# Sheet1.net
KiCad netlist of a schematic drawn in Altium Designer
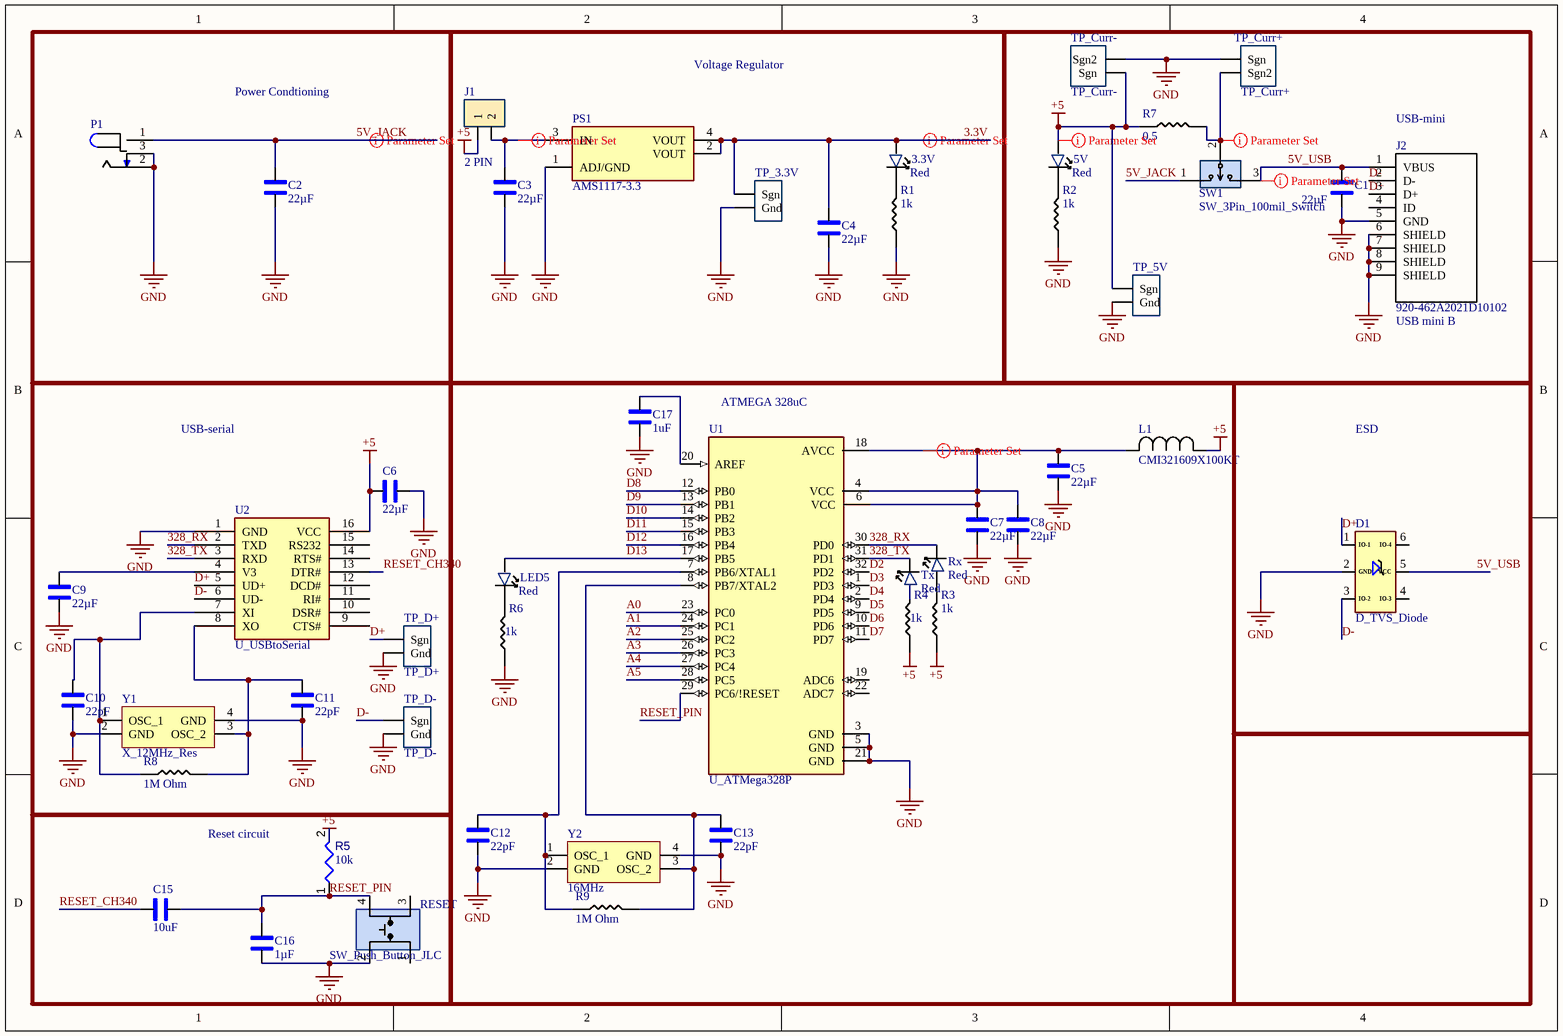
[diagram p0: Sheet1.SchDoc]

(export (version "E")
  (design (tool "Eeschema 10.0.6"))
  (components
    (comp (ref "3.3V")
      (value "Red")
      (footprint "LED_1206")
      (description "Red 621~631nm 1206 Light Emitting Diodes (LED) RoHS")
      (fields (field (name "LCSC PART#") "C93133") (field (name "MFR PART #") "15-21/R6C-FQ1R1B/2T"))
      (libsource (lib "University of Colorado") (part "LED_YELLOW_1206"))
    )
    (comp (ref "5V")
      (value "Red")
      (footprint "LED_1206")
      (description "Red 621~631nm 1206 Light Emitting Diodes (LED) RoHS")
      (fields (field (name "LCSC PART#") "C93133") (field (name "MFR PART #") "15-21/R6C-FQ1R1B/2T"))
      (libsource (lib "University of Colorado") (part "LED_YELLOW_1206"))
    )
    (comp (ref "C1")
      (value "22µF")
      (footprint "1206_Passive_Capacitor")
      (description "22uF ±10% 25V X5R 1206 Multilayer Ceramic Capacitors MLCC - SMD/SMT RoHS")
      (fields (field (name "LCSC PART#") "C12891") (field (name "MFR PART #") "CL31A226KAHNNNE"))
      (libsource (lib "University of Colorado") (part "C_47nF_1206"))
    )
    (comp (ref "C2")
      (value "22µF")
      (footprint "1206_Passive_Capacitor")
      (description "22uF ±10% 25V X5R 1206 Multilayer Ceramic Capacitors MLCC - SMD/SMT RoHS")
      (fields (field (name "LCSC PART#") "C12891") (field (name "MFR PART #") "CL31A226KAHNNNE"))
      (libsource (lib "University of Colorado") (part "C_47nF_1206"))
    )
    (comp (ref "C3")
      (value "22µF")
      (footprint "1206_Passive_Capacitor")
      (description "22uF ±10% 25V X5R 1206 Multilayer Ceramic Capacitors MLCC - SMD/SMT RoHS")
      (fields (field (name "LCSC PART#") "C12891") (field (name "MFR PART #") "CL31A226KAHNNNE"))
      (libsource (lib "University of Colorado") (part "C_47nF_1206"))
    )
    (comp (ref "C4")
      (value "22µF")
      (footprint "1206_Passive_Capacitor")
      (description "22uF ±10% 25V X5R 1206 Multilayer Ceramic Capacitors MLCC - SMD/SMT RoHS")
      (fields (field (name "LCSC PART#") "C12891") (field (name "MFR PART #") "CL31A226KAHNNNE"))
      (libsource (lib "University of Colorado") (part "C_47nF_1206"))
    )
    (comp (ref "C5")
      (value "22µF")
      (footprint "1206_Passive_Capacitor")
      (description "22uF ±10% 25V X5R 1206 Multilayer Ceramic Capacitors MLCC - SMD/SMT RoHS")
      (fields (field (name "LCSC PART#") "C12891") (field (name "MFR PART #") "CL31A226KAHNNNE"))
      (libsource (lib "University of Colorado") (part "C_47nF_1206"))
    )
    (comp (ref "C6")
      (value "22µF")
      (footprint "1206_Passive_Capacitor")
      (description "22uF ±10% 25V X5R 1206 Multilayer Ceramic Capacitors MLCC - SMD/SMT RoHS")
      (fields (field (name "LCSC PART#") "C12891") (field (name "MFR PART #") "CL31A226KAHNNNE"))
      (libsource (lib "University of Colorado") (part "C_47nF_1206"))
    )
    (comp (ref "C7")
      (value "22µF")
      (footprint "1206_Passive_Capacitor")
      (description "22uF ±10% 25V X5R 1206 Multilayer Ceramic Capacitors MLCC - SMD/SMT RoHS")
      (fields (field (name "LCSC PART#") "C12891") (field (name "MFR PART #") "CL31A226KAHNNNE"))
      (libsource (lib "University of Colorado") (part "C_47nF_1206"))
    )
    (comp (ref "C8")
      (value "22µF")
      (footprint "1206_Passive_Capacitor")
      (description "22uF ±10% 25V X5R 1206 Multilayer Ceramic Capacitors MLCC - SMD/SMT RoHS")
      (fields (field (name "LCSC PART#") "C12891") (field (name "MFR PART #") "CL31A226KAHNNNE"))
      (libsource (lib "University of Colorado") (part "C_47nF_1206"))
    )
    (comp (ref "C9")
      (value "22µF")
      (footprint "1206_Passive_Capacitor")
      (description "22uF ±10% 25V X5R 1206 Multilayer Ceramic Capacitors MLCC - SMD/SMT RoHS")
      (fields (field (name "LCSC PART#") "C12891") (field (name "MFR PART #") "CL31A226KAHNNNE"))
      (libsource (lib "University of Colorado") (part "C_47nF_1206"))
    )
    (comp (ref "C10")
      (value "22pF")
      (footprint "1206_Passive_Capacitor")
      (description "22uF ±10% 25V X5R 1206 Multilayer Ceramic Capacitors MLCC - SMD/SMT RoHS")
      (fields (field (name "LCSC PART#") "C12891") (field (name "MFR PART #") "CL31A226KAHNNNE"))
      (libsource (lib "University of Colorado") (part "C_47nF_1206"))
    )
    (comp (ref "C11")
      (value "22pF")
      (footprint "1206_Passive_Capacitor")
      (description "22uF ±10% 25V X5R 1206 Multilayer Ceramic Capacitors MLCC - SMD/SMT RoHS")
      (fields (field (name "LCSC PART#") "C12891") (field (name "MFR PART #") "CL31A226KAHNNNE"))
      (libsource (lib "University of Colorado") (part "C_47nF_1206"))
    )
    (comp (ref "C12")
      (value "22pF")
      (footprint "1206_Passive_Capacitor")
      (description "22uF ±10% 25V X5R 1206 Multilayer Ceramic Capacitors MLCC - SMD/SMT RoHS")
      (fields (field (name "LCSC PART#") "C12891") (field (name "MFR PART #") "CL31A226KAHNNNE"))
      (libsource (lib "University of Colorado") (part "C_47nF_1206"))
    )
    (comp (ref "C13")
      (value "22pF")
      (footprint "1206_Passive_Capacitor")
      (description "22uF ±10% 25V X5R 1206 Multilayer Ceramic Capacitors MLCC - SMD/SMT RoHS")
      (fields (field (name "LCSC PART#") "C12891") (field (name "MFR PART #") "CL31A226KAHNNNE"))
      (libsource (lib "University of Colorado") (part "C_47nF_1206"))
    )
    (comp (ref "C15")
      (value "10uF")
      (footprint "1206_Passive_Capacitor")
      (description "10uF ±10% 50V X5R 1206 Multilayer Ceramic Capacitors MLCC - SMD/SMT RoHS")
      (fields (field (name "LCSC PART#") "C13585") (field (name "MFR PART #") "CL31A106KBHNNNE"))
      (libsource (lib "ECEN5730Lib_2023_05_DS") (part "C_10uF_1206"))
    )
    (comp (ref "C16")
      (value "1µF")
      (footprint "1206_Passive_Capacitor")
      (description "MULTILAYER CERAMIC CAPACITORS MLCC - SMD/SMT 1UF 50V 1206 ROHS")
      (fields (field (name "MFR PART #") "CL31B105KBHNNNE") (field (name "LCSC PART#") "C1848"))
      (libsource (lib "University of Colorado") (part "C_47nF_1206"))
    )
    (comp (ref "C17")
      (value "1uF")
      (footprint "1206_Passive_Capacitor")
      (description "MULTILAYER CERAMIC CAPACITORS MLCC - SMD/SMT 1UF 50V 1206 ROHS")
      (fields (field (name "MFR PART #") "CL31B105KBHNNNE") (field (name "LCSC PART#") "C1848"))
      (libsource (lib "ECEN5730Lib_2023_05_DS") (part "C_1uF_1206"))
    )
    (comp (ref "D1")
      (value "D_TVS_Diode")
      (footprint "TVS")
      (description "TVS SOT-23-6 ROHS")
      (fields (field (name "LCSC PART#") "C85364") (field (name "MFR PART #") "SRV05-4-P-T7"))
      (libsource (lib "University of Colorado") (part "D_TVS_Diode"))
    )
    (comp (ref "J1")
      (value "2 PIN")
      (footprint "2_PIN_100MIL")
      (description "2.54mm Straight 2 1 Header,Breakaway Through Hole,P=2.54mm Pin Header & Female Header ROHS")
      (fields (field (name "LCSC PART#") "C124375") (field (name "MFR PART #") "B-2100S02P-A110"))
      (libsource (lib "University of Colorado") (part "JM_2_PIN_MALE"))
    )
    (comp (ref "J2")
      (value "USB mini B")
      (footprint "USB_MINI_B")
      (description "Through Hole USB Connectors RoHS")
      (fields
        (field (name "LCSC PART#") "C46398")
        (field (name "MFR PART #") "920-462A2021D10102")
        (field (name "Comment") "J_USB_B_Mini")
      )
      (libsource (lib "University of Colorado") (part "J_USB_B_Mini"))
    )
    (comp (ref "L1")
      (value "FB_10uH_1206")
      (footprint "AIML-1206_ABR-M")
      (description "25mA 10uH ±10% 800mO 1206  Inductors (SMD) ROHS")
      (fields (field (name "LCSC PART#") "C1051") (field (name "MFR PART #") "CMI321609X100KT"))
      (libsource (lib "University of Colorado") (part "FB_10uH_1206"))
    )
    (comp (ref "LED5")
      (value "Red")
      (footprint "LED_1206")
      (description "Red 621~631nm 1206 Light Emitting Diodes (LED) RoHS")
      (fields (field (name "LCSC PART#") "C93133") (field (name "MFR PART #") "15-21/R6C-FQ1R1B/2T"))
      (libsource (lib "University of Colorado") (part "LED_YELLOW_1206"))
    )
    (comp (ref "P1")
      (value "P_Power Jack")
      (footprint "Power_Jack")
      (description "Power Barrel Connector Jack 2.10mm ID (0.083\"), 5.50mm OD (0.217\") Through Hole, Right Angle")
      (fields (field (name "LCSC PART#") "C136744") (field (name "MFR PART #") "PJ-102A"))
      (libsource (lib "University of Colorado") (part "P_Power Jack"))
    )
    (comp (ref "PS1")
      (value "PS_AMS_LDO_3v3")
      (footprint "LDO")
      (description "LOW DROPOUT REGULATORS(LDO) POSITIVE FIXED 1.3V @ 800MA 15V 3.3V 1A SOT-223 ROHS")
      (fields (field (name "MFR PART #") "AMS1117-3.3") (field (name "LCSC PART#") "C6186"))
      (libsource (lib "University of Colorado") (part "PS_AMS_LDO_3v3"))
    )
    (comp (ref "R1")
      (value "1k")
      (footprint "1206_Passive_Resitor")
      (description "CHIP RESISTOR - SURFACE MOUNT 1KOHMS ±1% 1/4W 1206 ROHS")
      (fields (field (name "LCSC PART#") "C4410") (field (name "MFR PART #") "RNCP1206FTD1K00CT"))
      (libsource (lib "University of Colorado") (part "R_500mOhm_1206"))
    )
    (comp (ref "R2")
      (value "1k")
      (footprint "1206_Passive_Resitor")
      (description "CHIP RESISTOR - SURFACE MOUNT 1KOHMS ±1% 1/4W 1206 ROHS")
      (fields (field (name "LCSC PART#") "C4410") (field (name "MFR PART #") "RNCP1206FTD1K00CT"))
      (libsource (lib "University of Colorado") (part "R_500mOhm_1206"))
    )
    (comp (ref "R3")
      (value "1k")
      (footprint "1206_Passive_Resitor")
      (description "CHIP RESISTOR - SURFACE MOUNT 1KOHMS ±1% 1/4W 1206 ROHS")
      (fields (field (name "LCSC PART#") "C4410") (field (name "MFR PART #") "RNCP1206FTD1K00CT"))
      (libsource (lib "University of Colorado") (part "R_500mOhm_1206"))
    )
    (comp (ref "R4")
      (value "1k")
      (footprint "1206_Passive_Resitor")
      (description "CHIP RESISTOR - SURFACE MOUNT 1KOHMS ±1% 1/4W 1206 ROHS")
      (fields (field (name "LCSC PART#") "C4410") (field (name "MFR PART #") "RNCP1206FTD1K00CT"))
      (libsource (lib "University of Colorado") (part "R_500mOhm_1206"))
    )
    (comp (ref "R5")
      (value "10k")
      (footprint "RESC3216X60X45ML15T20")
      (description "Chip Resistor, 10 KOhm, +/- 1%, 0.25 W, -55 to 155 degC, 1206 (3216 Metric)")
      (fields (field (name "TOLERANCE") "1%") (field (name "POWER") "250mW"))
      (libsource (lib "University of Colorado") (part "RES-2"))
    )
    (comp (ref "R6")
      (value "1k")
      (footprint "1206_Passive_Resitor")
      (description "CHIP RESISTOR - SURFACE MOUNT 1KOHMS ±1% 1/4W 1206 ROHS")
      (fields (field (name "LCSC PART#") "C4410") (field (name "MFR PART #") "RNCP1206FTD1K00CT"))
      (libsource (lib "University of Colorado") (part "R_500mOhm_1206"))
    )
    (comp (ref "R7")
      (value "0.5")
      (footprint "1206_Passive_Resitor")
      (description "Resistors/Shunt 250mW 500mO ±800ppm/? ±5% 1206  Current Sense  Resistors ROHS")
      (fields (field (name "MFR PART #") "1206W4J050KT5E") (field (name "LCSC PART#") "C247433"))
      (libsource (lib "University of Colorado") (part "R_500mOhm_1206"))
    )
    (comp (ref "R8")
      (value "1M Ohm")
      (footprint "1206_Passive_Resitor")
      (description "CHIP RESISTOR - SURFACE MOUNT 1MOHMS ±1% 1/4W 1206 ROHS")
      (fields (field (name "MFR PART #") "RMCF1206JT1M00") (field (name "LCSC PART#") "C17927"))
      (libsource (lib "ECEN5730Lib_2023_05_DS") (part "R_1M_1206"))
    )
    (comp (ref "R9")
      (value "1M Ohm")
      (footprint "1206_Passive_Resitor")
      (description "CHIP RESISTOR - SURFACE MOUNT 1MOHMS ±1% 1/4W 1206 ROHS")
      (fields (field (name "MFR PART #") "RMCF1206JT1M00") (field (name "LCSC PART#") "C17927"))
      (libsource (lib "ECEN5730Lib_2023_05_DS") (part "R_1M_1206"))
    )
    (comp (ref "RESET")
      (value "SW_Push_Button_JLC")
      (footprint "Switch_JLC")
      (description "Tactile Switch SPST-NO Top Actuated Surface Mount")
      (fields (field (name "MFR PART #") "KH-4.5X4.5X4.3H-STM") (field (name "LCSC PART#") "C2837550"))
      (libsource (lib "University of Colorado") (part "SW_Push_Button_JLC"))
    )
    (comp (ref "Rx")
      (value "Red")
      (footprint "LED_1206")
      (description "Red 621~631nm 1206 Light Emitting Diodes (LED) RoHS")
      (fields (field (name "LCSC PART#") "C93133") (field (name "MFR PART #") "15-21/R6C-FQ1R1B/2T"))
      (libsource (lib "University of Colorado") (part "LED_YELLOW_1206"))
    )
    (comp (ref "SW1")
      (value "SW_3Pin_100mil_Switch")
      (footprint "3_PIN_100mil")
      (description "Connector Header Through Hole 3 position 0.100\" (2.54mm)")
      (fields (field (name "LCSC PART#") "C49257") (field (name "MFR PART #") "PREC003SAAN-RC"))
      (libsource (lib "University of Colorado") (part "SW_3Pin_100mil_Switch"))
    )
    (comp (ref "TP_3.3V")
      (value "TP_10x_Probe")
      (footprint "TP10x_Probe")
      (description "Test Point 300 mil centers")
      (libsource (lib "University of Colorado") (part "TP_10x_Probe"))
    )
    (comp (ref "TP_5V")
      (value "TP_10x_Probe")
      (footprint "TP10x_Probe")
      (description "Test Point 300 mil centers")
      (libsource (lib "University of Colorado") (part "TP_10x_Probe"))
    )
    (comp (ref "TP_Curr+")
      (value "TP_Curr+")
      (footprint "TP_Diff_Probe")
      (description "Test Point 300 mil centers")
      (libsource (lib "") (part "TP_Diff_Probe_1"))
    )
    (comp (ref "TP_Curr-")
      (value "TP_Curr-")
      (footprint "TP_Diff_Probe")
      (description "Test Point 300 mil centers")
      (libsource (lib "University of Colorado") (part "TP_Diff_Probe"))
    )
    (comp (ref "TP_D+")
      (value "TP_D+")
      (footprint "TP10x_Probe")
      (description "Test Point 300 mil centers")
      (libsource (lib "University of Colorado") (part "TP_10x_Probe"))
    )
    (comp (ref "TP_D-")
      (value "TP_D-")
      (footprint "TP10x_Probe")
      (description "Test Point 300 mil centers")
      (libsource (lib "University of Colorado") (part "TP_10x_Probe"))
    )
    (comp (ref "Tx")
      (value "Red")
      (footprint "LED_1206")
      (description "Red 621~631nm 1206 Light Emitting Diodes (LED) RoHS")
      (fields (field (name "LCSC PART#") "C93133") (field (name "MFR PART #") "15-21/R6C-FQ1R1B/2T"))
      (libsource (lib "University of Colorado") (part "LED_YELLOW_1206"))
    )
    (comp (ref "U1")
      (value "U_ATMega328P")
      (footprint "ATMega328P")
      (description "AVR AVR® ATmega Microcontroller IC 8-Bit 20MHz 32KB (16K x 16) FLASH 32-TQFP (7x7)")
      (fields (field (name "MFR PART #") "ATMEGA328P-AU") (field (name "LCSC PART#") "C14877"))
      (libsource (lib "University of Colorado") (part "U_ATMega328P"))
    )
    (comp (ref "U2")
      (value "U_USBtoSerial")
      (footprint "USB to serial")
      (description "Transceiver USB 2.0 2Mbps SOP-16_150mil USB ICs RoHS")
      (fields (field (name "LCSC PART#") "C14267") (field (name "MFR PART #") "CH340G"))
      (libsource (lib "University of Colorado") (part "U_USBtoSerial"))
    )
    (comp (ref "Y1")
      (value "X_12MHz_Res")
      (footprint "Crystal resonator")
      (description "SMD Crystal Resonators 12MHz ±10ppm SMD-3225_4P RoHS")
      (fields (field (name "MFR PART #") "X322512MSB4SI") (field (name "LCSC PART#") "C9002"))
      (libsource (lib "University of Colorado") (part "X_12MHz_Res"))
    )
    (comp (ref "Y2")
      (value "16MHz")
      (footprint "Crystal resonator")
      (description "±10ppm 16000000Hz -40℃~85℃ 贴片无源晶振 60Ω 9pF SMD3225-4P Crystals ROHS")
      (fields (field (name "LCSC PART#") "C13738") (field (name "MFR PART #") "X322516MLB4SI"))
      (libsource (lib "ECEN5730Lib_2023_05_DS") (part "X_16Mhz_Res"))
    )
  )
  (nets
    (net (code "1") (name "+5") (class "Default")
      (node (ref "5V") (pin "1") (pinfunction "1_1") (pintype "passive"))
      (node (ref "C6") (pin "1") (pinfunction "1_1") (pintype "passive"))
      (node (ref "J1") (pin "1") (pinfunction "1_1") (pintype "passive"))
      (node (ref "L1") (pin "1") (pinfunction "1_1") (pintype "passive"))
      (node (ref "R3") (pin "1") (pinfunction "1_1") (pintype "passive"))
      (node (ref "R4") (pin "1") (pinfunction "1_1") (pintype "passive"))
      (node (ref "R5") (pin "2") (pinfunction "2_2") (pintype "passive"))
      (node (ref "R7") (pin "1") (pinfunction "1_1") (pintype "passive"))
      (node (ref "TP_5V") (pin "1") (pinfunction "Sgn_1") (pintype "passive"))
      (node (ref "TP_Curr-") (pin "1") (pinfunction "Sgn_1") (pintype "passive"))
      (node (ref "U2") (pin "16") (pinfunction "VCC_16") (pintype "passive"))
    )
    (net (code "2") (name "/3.3V") (class "Default")
      (node (ref "3.3V") (pin "1") (pinfunction "1_1") (pintype "passive"))
      (node (ref "C4") (pin "1") (pinfunction "1_1") (pintype "passive"))
      (node (ref "PS1") (pin "2") (pinfunction "VOUT_2") (pintype "power_in"))
      (node (ref "PS1") (pin "4") (pinfunction "VOUT_4") (pintype "power_in"))
      (node (ref "TP_3.3V") (pin "1") (pinfunction "Sgn_1") (pintype "passive"))
    )
    (net (code "3") (name "/5V_JACK") (class "Default")
      (node (ref "C2") (pin "2") (pinfunction "2_2") (pintype "passive"))
      (node (ref "P1") (pin "1") (pinfunction "1_1") (pintype "power_in"))
      (node (ref "SW1") (pin "1") (pinfunction "1_1") (pintype "passive"))
    )
    (net (code "4") (name "/5V_USB") (class "Default")
      (node (ref "C1") (pin "2") (pinfunction "2_2") (pintype "passive"))
      (node (ref "D1") (pin "5") (pinfunction "VCC_5") (pintype "passive"))
      (node (ref "J2") (pin "1") (pinfunction "VBUS_1") (pintype "passive"))
      (node (ref "SW1") (pin "3") (pinfunction "3_3") (pintype "passive"))
    )
    (net (code "5") (name "/328_RX") (class "Default")
      (node (ref "Rx") (pin "2") (pinfunction "2_2") (pintype "passive"))
      (node (ref "U1") (pin "30") (pinfunction "PD0_30") (pintype "bidirectional"))
      (node (ref "U2") (pin "2") (pinfunction "TXD_2") (pintype "passive"))
    )
    (net (code "6") (name "/328_TX") (class "Default")
      (node (ref "Tx") (pin "2") (pinfunction "2_2") (pintype "passive"))
      (node (ref "U1") (pin "31") (pinfunction "PD1_31") (pintype "bidirectional"))
      (node (ref "U2") (pin "3") (pinfunction "RXD_3") (pintype "passive"))
    )
    (net (code "7") (name "/A0") (class "Default")
      (node (ref "U1") (pin "23") (pinfunction "PC0_23") (pintype "bidirectional"))
    )
    (net (code "8") (name "/A1") (class "Default")
      (node (ref "U1") (pin "24") (pinfunction "PC1_24") (pintype "bidirectional"))
    )
    (net (code "9") (name "/A2") (class "Default")
      (node (ref "U1") (pin "25") (pinfunction "PC2_25") (pintype "bidirectional"))
    )
    (net (code "10") (name "/A3") (class "Default")
      (node (ref "U1") (pin "26") (pinfunction "PC3_26") (pintype "bidirectional"))
    )
    (net (code "11") (name "/A4") (class "Default")
      (node (ref "U1") (pin "27") (pinfunction "PC4_27") (pintype "bidirectional"))
    )
    (net (code "12") (name "/A5") (class "Default")
      (node (ref "U1") (pin "28") (pinfunction "PC5_28") (pintype "bidirectional"))
    )
    (net (code "13") (name "/D+") (class "Default")
      (node (ref "D1") (pin "1") (pinfunction "IO-1_1") (pintype "passive"))
      (node (ref "J2") (pin "3") (pinfunction "D+_3") (pintype "passive"))
      (node (ref "TP_D+") (pin "1") (pinfunction "Sgn_1") (pintype "passive"))
      (node (ref "U2") (pin "5") (pinfunction "UD+_5") (pintype "passive"))
    )
    (net (code "14") (name "/D-") (class "Default")
      (node (ref "D1") (pin "3") (pinfunction "IO-2_3") (pintype "passive"))
      (node (ref "J2") (pin "2") (pinfunction "D-_2") (pintype "passive"))
      (node (ref "TP_D-") (pin "1") (pinfunction "Sgn_1") (pintype "passive"))
      (node (ref "U2") (pin "6") (pinfunction "UD-_6") (pintype "passive"))
    )
    (net (code "15") (name "/D2") (class "Default")
      (node (ref "U1") (pin "32") (pinfunction "PD2_32") (pintype "bidirectional"))
    )
    (net (code "16") (name "/D3") (class "Default")
      (node (ref "U1") (pin "1") (pinfunction "PD3_1") (pintype "bidirectional"))
    )
    (net (code "17") (name "/D4") (class "Default")
      (node (ref "U1") (pin "2") (pinfunction "PD4_2") (pintype "bidirectional"))
    )
    (net (code "18") (name "/D5") (class "Default")
      (node (ref "U1") (pin "9") (pinfunction "PD5_9") (pintype "bidirectional"))
    )
    (net (code "19") (name "/D6") (class "Default")
      (node (ref "U1") (pin "10") (pinfunction "PD6_10") (pintype "bidirectional"))
    )
    (net (code "20") (name "/D7") (class "Default")
      (node (ref "U1") (pin "11") (pinfunction "PD7_11") (pintype "bidirectional"))
    )
    (net (code "21") (name "/D8") (class "Default")
      (node (ref "U1") (pin "12") (pinfunction "PB0_12") (pintype "bidirectional"))
    )
    (net (code "22") (name "/D9") (class "Default")
      (node (ref "U1") (pin "13") (pinfunction "PB1_13") (pintype "bidirectional"))
    )
    (net (code "23") (name "/D10") (class "Default")
      (node (ref "U1") (pin "14") (pinfunction "PB2_14") (pintype "bidirectional"))
    )
    (net (code "24") (name "/D11") (class "Default")
      (node (ref "U1") (pin "15") (pinfunction "PB3_15") (pintype "bidirectional"))
    )
    (net (code "25") (name "/D12") (class "Default")
      (node (ref "U1") (pin "16") (pinfunction "PB4_16") (pintype "bidirectional"))
    )
    (net (code "26") (name "/D13") (class "Default")
      (node (ref "LED5") (pin "1") (pinfunction "1_1") (pintype "passive"))
      (node (ref "U1") (pin "17") (pinfunction "PB5_17") (pintype "bidirectional"))
    )
    (net (code "27") (name "/RESET_CH340") (class "Default")
      (node (ref "C15") (pin "1") (pinfunction "1_1") (pintype "passive"))
      (node (ref "U2") (pin "13") (pinfunction "DTR#_13") (pintype "passive"))
    )
    (net (code "28") (name "/RESET_PIN") (class "Default")
      (node (ref "C15") (pin "2") (pinfunction "2_2") (pintype "passive"))
      (node (ref "C16") (pin "2") (pinfunction "2_2") (pintype "passive"))
      (node (ref "R5") (pin "1") (pinfunction "1_1") (pintype "passive"))
      (node (ref "RESET") (pin "4") (pinfunction "4_4") (pintype "passive"))
      (node (ref "U1") (pin "29") (pinfunction "PC6/!RESET_29") (pintype "bidirectional"))
    )
    (net (code "29") (name "GND") (class "Default")
      (node (ref "C1") (pin "1") (pinfunction "1_1") (pintype "passive"))
      (node (ref "C10") (pin "1") (pinfunction "1_1") (pintype "passive"))
      (node (ref "C11") (pin "1") (pinfunction "1_1") (pintype "passive"))
      (node (ref "C12") (pin "1") (pinfunction "1_1") (pintype "passive"))
      (node (ref "C13") (pin "1") (pinfunction "1_1") (pintype "passive"))
      (node (ref "C16") (pin "1") (pinfunction "1_1") (pintype "passive"))
      (node (ref "C17") (pin "2") (pinfunction "2_2") (pintype "passive"))
      (node (ref "C2") (pin "1") (pinfunction "1_1") (pintype "passive"))
      (node (ref "C3") (pin "2") (pinfunction "2_2") (pintype "passive"))
      (node (ref "C4") (pin "2") (pinfunction "2_2") (pintype "passive"))
      (node (ref "C5") (pin "1") (pinfunction "1_1") (pintype "passive"))
      (node (ref "C6") (pin "2") (pinfunction "2_2") (pintype "passive"))
      (node (ref "C7") (pin "1") (pinfunction "1_1") (pintype "passive"))
      (node (ref "C8") (pin "1") (pinfunction "1_1") (pintype "passive"))
      (node (ref "C9") (pin "2") (pinfunction "2_2") (pintype "passive"))
      (node (ref "D1") (pin "2") (pinfunction "GND_2") (pintype "passive"))
      (node (ref "J2") (pin "5") (pinfunction "GND_5") (pintype "passive"))
      (node (ref "J2") (pin "6") (pinfunction "SHIELD_6") (pintype "passive"))
      (node (ref "J2") (pin "7") (pinfunction "SHIELD_7") (pintype "passive"))
      (node (ref "J2") (pin "8") (pinfunction "SHIELD_8") (pintype "passive"))
      (node (ref "J2") (pin "9") (pinfunction "SHIELD_9") (pintype "passive"))
      (node (ref "P1") (pin "2") (pinfunction "2_2") (pintype "power_in"))
      (node (ref "P1") (pin "3") (pinfunction "3_3") (pintype "power_in"))
      (node (ref "PS1") (pin "1") (pinfunction "ADJ/GND_1") (pintype "passive"))
      (node (ref "R1") (pin "1") (pinfunction "1_1") (pintype "passive"))
      (node (ref "R2") (pin "1") (pinfunction "1_1") (pintype "passive"))
      (node (ref "R6") (pin "1") (pinfunction "1_1") (pintype "passive"))
      (node (ref "RESET") (pin "2") (pinfunction "2_2") (pintype "passive"))
      (node (ref "TP_3.3V") (pin "2") (pinfunction "Gnd_2") (pintype "passive"))
      (node (ref "TP_5V") (pin "2") (pinfunction "Gnd_2") (pintype "passive"))
      (node (ref "TP_Curr+") (pin "1") (pinfunction "Sgn_1") (pintype "passive"))
      (node (ref "TP_Curr-") (pin "2") (pinfunction "Sgn2_2") (pintype "passive"))
      (node (ref "TP_D+") (pin "2") (pinfunction "Gnd_2") (pintype "passive"))
      (node (ref "TP_D-") (pin "2") (pinfunction "Gnd_2") (pintype "passive"))
      (node (ref "U1") (pin "21") (pinfunction "GND_21") (pintype "power_in"))
      (node (ref "U1") (pin "3") (pinfunction "GND_3") (pintype "power_in"))
      (node (ref "U1") (pin "5") (pinfunction "GND_5") (pintype "power_in"))
      (node (ref "U2") (pin "1") (pinfunction "GND_1") (pintype "passive"))
      (node (ref "Y1") (pin "2") (pinfunction "GND_2") (pintype "passive"))
      (node (ref "Y1") (pin "4") (pinfunction "GND_4") (pintype "passive"))
      (node (ref "Y2") (pin "2") (pinfunction "GND_2") (pintype "passive"))
      (node (ref "Y2") (pin "4") (pinfunction "GND_4") (pintype "passive"))
    )
    (net (code "30") (name "Net-(3.3V-Pad2)") (class "Default")
      (node (ref "3.3V") (pin "2") (pinfunction "2_2") (pintype "passive"))
      (node (ref "R1") (pin "2") (pinfunction "2_2") (pintype "passive"))
    )
    (net (code "31") (name "Net-(5V-Pad2)") (class "Default")
      (node (ref "5V") (pin "2") (pinfunction "2_2") (pintype "passive"))
      (node (ref "R2") (pin "2") (pinfunction "2_2") (pintype "passive"))
    )
    (net (code "32") (name "Net-(LED5-Pad2)") (class "Default")
      (node (ref "LED5") (pin "2") (pinfunction "2_2") (pintype "passive"))
      (node (ref "R6") (pin "2") (pinfunction "2_2") (pintype "passive"))
    )
    (net (code "33") (name "Net-(PS1-IN)") (class "Default")
      (node (ref "C3") (pin "1") (pinfunction "1_1") (pintype "passive"))
      (node (ref "J1") (pin "2") (pinfunction "2_2") (pintype "passive"))
      (node (ref "PS1") (pin "3") (pinfunction "IN_3") (pintype "power_in"))
    )
    (net (code "34") (name "Net-(R3-Pad2)") (class "Default")
      (node (ref "R3") (pin "2") (pinfunction "2_2") (pintype "passive"))
      (node (ref "Rx") (pin "1") (pinfunction "1_1") (pintype "passive"))
    )
    (net (code "35") (name "Net-(R4-Pad2)") (class "Default")
      (node (ref "R4") (pin "2") (pinfunction "2_2") (pintype "passive"))
      (node (ref "Tx") (pin "1") (pinfunction "1_1") (pintype "passive"))
    )
    (net (code "36") (name "Net-(TP_Curr+-Sgn2)") (class "Default")
      (node (ref "R7") (pin "2") (pinfunction "2_2") (pintype "passive"))
      (node (ref "SW1") (pin "2") (pinfunction "2_2") (pintype "passive"))
      (node (ref "TP_Curr+") (pin "2") (pinfunction "Sgn2_2") (pintype "passive"))
    )
    (net (code "37") (name "Net-(U1-AREF)") (class "Default")
      (node (ref "C17") (pin "1") (pinfunction "1_1") (pintype "passive"))
      (node (ref "U1") (pin "20") (pinfunction "AREF_20") (pintype "input"))
    )
    (net (code "38") (name "Net-(U1-AVCC)") (class "Default")
      (node (ref "C5") (pin "2") (pinfunction "2_2") (pintype "passive"))
      (node (ref "C7") (pin "2") (pinfunction "2_2") (pintype "passive"))
      (node (ref "C8") (pin "2") (pinfunction "2_2") (pintype "passive"))
      (node (ref "L1") (pin "2") (pinfunction "2_2") (pintype "passive"))
      (node (ref "U1") (pin "18") (pinfunction "AVCC_18") (pintype "power_in"))
      (node (ref "U1") (pin "4") (pinfunction "VCC_4") (pintype "power_in"))
      (node (ref "U1") (pin "6") (pinfunction "VCC_6") (pintype "power_in"))
    )
    (net (code "39") (name "Net-(U1-PB6{slash}XTAL1)") (class "Default")
      (node (ref "C12") (pin "2") (pinfunction "2_2") (pintype "passive"))
      (node (ref "R9") (pin "1") (pinfunction "1_1") (pintype "passive"))
      (node (ref "U1") (pin "7") (pinfunction "PB6/XTAL1_7") (pintype "bidirectional"))
      (node (ref "Y2") (pin "1") (pinfunction "OSC_1_1") (pintype "passive"))
    )
    (net (code "40") (name "Net-(U1-PB7{slash}XTAL2)") (class "Default")
      (node (ref "C13") (pin "2") (pinfunction "2_2") (pintype "passive"))
      (node (ref "R9") (pin "2") (pinfunction "2_2") (pintype "passive"))
      (node (ref "U1") (pin "8") (pinfunction "PB7/XTAL2_8") (pintype "bidirectional"))
      (node (ref "Y2") (pin "3") (pinfunction "OSC_2_3") (pintype "passive"))
    )
    (net (code "41") (name "Net-(U2-V3)") (class "Default")
      (node (ref "C9") (pin "1") (pinfunction "1_1") (pintype "passive"))
      (node (ref "U2") (pin "4") (pinfunction "V3_4") (pintype "passive"))
    )
    (net (code "42") (name "Net-(U2-XI)") (class "Default")
      (node (ref "C10") (pin "2") (pinfunction "2_2") (pintype "passive"))
      (node (ref "R8") (pin "1") (pinfunction "1_1") (pintype "passive"))
      (node (ref "U2") (pin "7") (pinfunction "XI_7") (pintype "passive"))
      (node (ref "Y1") (pin "1") (pinfunction "OSC_1_1") (pintype "passive"))
    )
    (net (code "43") (name "Net-(U2-XO)") (class "Default")
      (node (ref "C11") (pin "2") (pinfunction "2_2") (pintype "passive"))
      (node (ref "R8") (pin "2") (pinfunction "2_2") (pintype "passive"))
      (node (ref "U2") (pin "8") (pinfunction "XO_8") (pintype "passive"))
      (node (ref "Y1") (pin "3") (pinfunction "OSC_2_3") (pintype "passive"))
    )
    (net (code "44") (name "unconnected-(D1-IO-3-Pad4)") (class "Default")
      (node (ref "D1") (pin "4") (pinfunction "IO-3_4") (pintype "passive"))
    )
    (net (code "45") (name "unconnected-(D1-IO-4-Pad6)") (class "Default")
      (node (ref "D1") (pin "6") (pinfunction "IO-4_6") (pintype "passive"))
    )
    (net (code "46") (name "unconnected-(J2-ID-Pad4)") (class "Default")
      (node (ref "J2") (pin "4") (pinfunction "ID_4") (pintype "passive"))
    )
    (net (code "47") (name "unconnected-(RESET-Pad1)") (class "Default")
      (node (ref "RESET") (pin "1") (pinfunction "1_1") (pintype "passive"))
    )
    (net (code "48") (name "unconnected-(RESET-Pad3)") (class "Default")
      (node (ref "RESET") (pin "3") (pinfunction "3_3") (pintype "passive"))
    )
    (net (code "49") (name "unconnected-(U1-ADC6-Pad19)") (class "Default")
      (node (ref "U1") (pin "19") (pinfunction "ADC6_19") (pintype "bidirectional"))
    )
    (net (code "50") (name "unconnected-(U1-ADC7-Pad22)") (class "Default")
      (node (ref "U1") (pin "22") (pinfunction "ADC7_22") (pintype "bidirectional"))
    )
    (net (code "51") (name "unconnected-(U2-CTS#-Pad9)") (class "Default")
      (node (ref "U2") (pin "9") (pinfunction "CTS#_9") (pintype "passive"))
    )
    (net (code "52") (name "unconnected-(U2-DCD#-Pad12)") (class "Default")
      (node (ref "U2") (pin "12") (pinfunction "DCD#_12") (pintype "passive"))
    )
    (net (code "53") (name "unconnected-(U2-DSR#-Pad10)") (class "Default")
      (node (ref "U2") (pin "10") (pinfunction "DSR#_10") (pintype "passive"))
    )
    (net (code "54") (name "unconnected-(U2-RI#-Pad11)") (class "Default")
      (node (ref "U2") (pin "11") (pinfunction "RI#_11") (pintype "passive"))
    )
    (net (code "55") (name "unconnected-(U2-RS232-Pad15)") (class "Default")
      (node (ref "U2") (pin "15") (pinfunction "RS232_15") (pintype "passive"))
    )
    (net (code "56") (name "unconnected-(U2-RTS#-Pad14)") (class "Default")
      (node (ref "U2") (pin "14") (pinfunction "RTS#_14") (pintype "passive"))
    )
  )
)
